# ERC_Sch.net
KiCad netlist of a schematic drawn in EAGLE
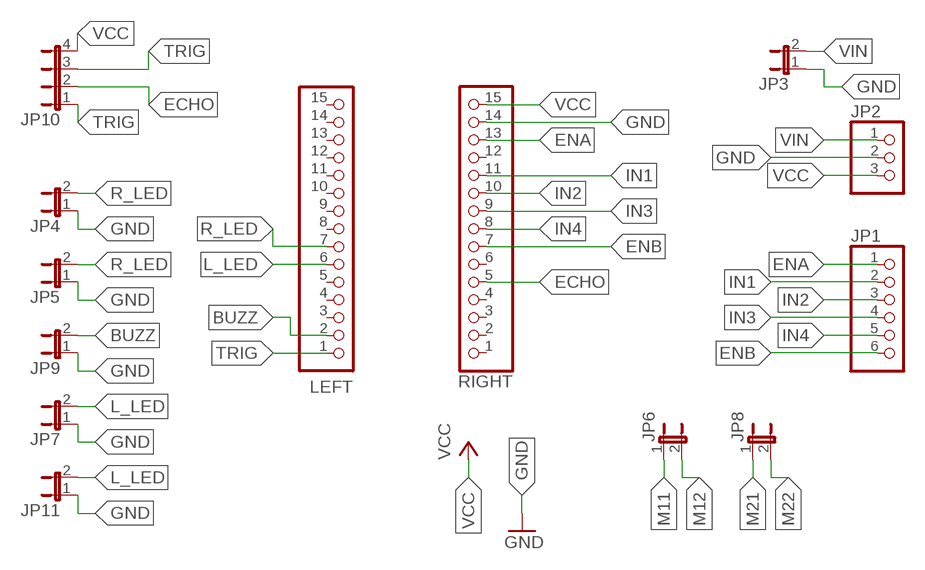
[diagram p0: schematic, sheet 1]

(export (version "E")
  (design (tool "Eeschema 10.0.6"))
  (components
    (comp (ref "JP1")
      (value "PINHD-1X6")
      (footprint "eagle-import:1X06")
      (libsource (lib "eagle-import") (part "PINHD-1X6"))
    )
    (comp (ref "JP2")
      (value "PINHD-1X3")
      (footprint "eagle-import:1X03")
      (libsource (lib "eagle-import") (part "PINHD-1X3"))
    )
    (comp (ref "JP3")
      (value "JP1E")
      (footprint "eagle-import:JP1")
      (libsource (lib "eagle-import") (part "JP1E"))
    )
    (comp (ref "JP4")
      (value "JP1E")
      (footprint "eagle-import:JP1")
      (libsource (lib "eagle-import") (part "JP1E"))
    )
    (comp (ref "JP5")
      (value "JP1E")
      (footprint "eagle-import:JP1")
      (libsource (lib "eagle-import") (part "JP1E"))
    )
    (comp (ref "JP6")
      (value "JP1E")
      (footprint "eagle-import:JP1")
      (libsource (lib "eagle-import") (part "JP1E"))
    )
    (comp (ref "JP7")
      (value "JP1E")
      (footprint "eagle-import:JP1")
      (libsource (lib "eagle-import") (part "JP1E"))
    )
    (comp (ref "JP8")
      (value "JP1E")
      (footprint "eagle-import:JP1")
      (libsource (lib "eagle-import") (part "JP1E"))
    )
    (comp (ref "JP9")
      (value "JP1E")
      (footprint "eagle-import:JP1")
      (libsource (lib "eagle-import") (part "JP1E"))
    )
    (comp (ref "JP10")
      (value "JP4E")
      (footprint "eagle-import:JP4")
      (libsource (lib "eagle-import") (part "JP4E"))
    )
    (comp (ref "JP11")
      (value "JP1E")
      (footprint "eagle-import:JP1")
      (libsource (lib "eagle-import") (part "JP1E"))
    )
    (comp (ref "LEFT")
      (value "PINHD-1X15")
      (footprint "eagle-import:1X15")
      (libsource (lib "eagle-import") (part "PINHD-1X15"))
    )
    (comp (ref "RIGHT")
      (value "PINHD-1X15")
      (footprint "eagle-import:1X15")
      (libsource (lib "eagle-import") (part "PINHD-1X15"))
    )
  )
  (nets
    (net (code "1") (name "BUZZ") (class "Default")
      (node (ref "JP9") (pin "2") (pinfunction "2_2") (pintype "passive"))
      (node (ref "LEFT") (pin "2") (pinfunction "2_2") (pintype "passive"))
    )
    (net (code "2") (name "ECHO") (class "Default")
      (node (ref "JP10") (pin "2") (pinfunction "2_2") (pintype "passive"))
      (node (ref "RIGHT") (pin "5") (pinfunction "5_5") (pintype "passive"))
    )
    (net (code "3") (name "ENA") (class "Default")
      (node (ref "JP1") (pin "1") (pinfunction "1_1") (pintype "passive"))
      (node (ref "RIGHT") (pin "13") (pinfunction "13_13") (pintype "passive"))
    )
    (net (code "4") (name "ENB") (class "Default")
      (node (ref "JP1") (pin "6") (pinfunction "6_6") (pintype "passive"))
      (node (ref "RIGHT") (pin "7") (pinfunction "7_7") (pintype "passive"))
    )
    (net (code "5") (name "GND") (class "Default")
      (node (ref "JP11") (pin "1") (pinfunction "1_1") (pintype "passive"))
      (node (ref "JP2") (pin "2") (pinfunction "2_2") (pintype "passive"))
      (node (ref "JP3") (pin "1") (pinfunction "1_1") (pintype "passive"))
      (node (ref "JP4") (pin "1") (pinfunction "1_1") (pintype "passive"))
      (node (ref "JP5") (pin "1") (pinfunction "1_1") (pintype "passive"))
      (node (ref "JP7") (pin "1") (pinfunction "1_1") (pintype "passive"))
      (node (ref "JP9") (pin "1") (pinfunction "1_1") (pintype "passive"))
      (node (ref "RIGHT") (pin "14") (pinfunction "14_14") (pintype "passive"))
    )
    (net (code "6") (name "IN1") (class "Default")
      (node (ref "JP1") (pin "2") (pinfunction "2_2") (pintype "passive"))
      (node (ref "RIGHT") (pin "11") (pinfunction "11_11") (pintype "passive"))
    )
    (net (code "7") (name "IN2") (class "Default")
      (node (ref "JP1") (pin "3") (pinfunction "3_3") (pintype "passive"))
      (node (ref "RIGHT") (pin "10") (pinfunction "10_10") (pintype "passive"))
    )
    (net (code "8") (name "IN3") (class "Default")
      (node (ref "JP1") (pin "4") (pinfunction "4_4") (pintype "passive"))
      (node (ref "RIGHT") (pin "9") (pinfunction "9_9") (pintype "passive"))
    )
    (net (code "9") (name "IN4") (class "Default")
      (node (ref "JP1") (pin "5") (pinfunction "5_5") (pintype "passive"))
      (node (ref "RIGHT") (pin "8") (pinfunction "8_8") (pintype "passive"))
    )
    (net (code "10") (name "L_LED") (class "Default")
      (node (ref "JP11") (pin "2") (pinfunction "2_2") (pintype "passive"))
      (node (ref "JP7") (pin "2") (pinfunction "2_2") (pintype "passive"))
      (node (ref "LEFT") (pin "6") (pinfunction "6_6") (pintype "passive"))
    )
    (net (code "11") (name "M11") (class "Default")
      (node (ref "JP6") (pin "1") (pinfunction "1_1") (pintype "passive"))
    )
    (net (code "12") (name "M12") (class "Default")
      (node (ref "JP6") (pin "2") (pinfunction "2_2") (pintype "passive"))
    )
    (net (code "13") (name "M21") (class "Default")
      (node (ref "JP8") (pin "1") (pinfunction "1_1") (pintype "passive"))
    )
    (net (code "14") (name "M22") (class "Default")
      (node (ref "JP8") (pin "2") (pinfunction "2_2") (pintype "passive"))
    )
    (net (code "15") (name "R_LED") (class "Default")
      (node (ref "JP4") (pin "2") (pinfunction "2_2") (pintype "passive"))
      (node (ref "JP5") (pin "2") (pinfunction "2_2") (pintype "passive"))
      (node (ref "LEFT") (pin "7") (pinfunction "7_7") (pintype "passive"))
    )
    (net (code "16") (name "TRIG") (class "Default")
      (node (ref "JP10") (pin "1") (pinfunction "1_1") (pintype "passive"))
      (node (ref "JP10") (pin "3") (pinfunction "3_3") (pintype "passive"))
      (node (ref "LEFT") (pin "1") (pinfunction "1_1") (pintype "passive"))
    )
    (net (code "17") (name "VCC") (class "Default")
      (node (ref "JP10") (pin "4") (pinfunction "4_4") (pintype "passive"))
      (node (ref "JP2") (pin "3") (pinfunction "3_3") (pintype "passive"))
      (node (ref "RIGHT") (pin "15") (pinfunction "15_15") (pintype "passive"))
    )
    (net (code "18") (name "VIN") (class "Default")
      (node (ref "JP2") (pin "1") (pinfunction "1_1") (pintype "passive"))
      (node (ref "JP3") (pin "2") (pinfunction "2_2") (pintype "passive"))
    )
    (net (code "19") (name "unconnected-(LEFT-Pad3)") (class "Default")
      (node (ref "LEFT") (pin "3") (pinfunction "3_3") (pintype "passive"))
    )
    (net (code "20") (name "unconnected-(LEFT-Pad4)") (class "Default")
      (node (ref "LEFT") (pin "4") (pinfunction "4_4") (pintype "passive"))
    )
    (net (code "21") (name "unconnected-(LEFT-Pad5)") (class "Default")
      (node (ref "LEFT") (pin "5") (pinfunction "5_5") (pintype "passive"))
    )
    (net (code "22") (name "unconnected-(LEFT-Pad8)") (class "Default")
      (node (ref "LEFT") (pin "8") (pinfunction "8_8") (pintype "passive"))
    )
    (net (code "23") (name "unconnected-(LEFT-Pad9)") (class "Default")
      (node (ref "LEFT") (pin "9") (pinfunction "9_9") (pintype "passive"))
    )
    (net (code "24") (name "unconnected-(LEFT-Pad10)") (class "Default")
      (node (ref "LEFT") (pin "10") (pinfunction "10_10") (pintype "passive"))
    )
    (net (code "25") (name "unconnected-(LEFT-Pad11)") (class "Default")
      (node (ref "LEFT") (pin "11") (pinfunction "11_11") (pintype "passive"))
    )
    (net (code "26") (name "unconnected-(LEFT-Pad12)") (class "Default")
      (node (ref "LEFT") (pin "12") (pinfunction "12_12") (pintype "passive"))
    )
    (net (code "27") (name "unconnected-(LEFT-Pad13)") (class "Default")
      (node (ref "LEFT") (pin "13") (pinfunction "13_13") (pintype "passive"))
    )
    (net (code "28") (name "unconnected-(LEFT-Pad14)") (class "Default")
      (node (ref "LEFT") (pin "14") (pinfunction "14_14") (pintype "passive"))
    )
    (net (code "29") (name "unconnected-(LEFT-Pad15)") (class "Default")
      (node (ref "LEFT") (pin "15") (pinfunction "15_15") (pintype "passive"))
    )
    (net (code "30") (name "unconnected-(RIGHT-Pad1)") (class "Default")
      (node (ref "RIGHT") (pin "1") (pinfunction "1_1") (pintype "passive"))
    )
    (net (code "31") (name "unconnected-(RIGHT-Pad2)") (class "Default")
      (node (ref "RIGHT") (pin "2") (pinfunction "2_2") (pintype "passive"))
    )
    (net (code "32") (name "unconnected-(RIGHT-Pad3)") (class "Default")
      (node (ref "RIGHT") (pin "3") (pinfunction "3_3") (pintype "passive"))
    )
    (net (code "33") (name "unconnected-(RIGHT-Pad4)") (class "Default")
      (node (ref "RIGHT") (pin "4") (pinfunction "4_4") (pintype "passive"))
    )
    (net (code "34") (name "unconnected-(RIGHT-Pad6)") (class "Default")
      (node (ref "RIGHT") (pin "6") (pinfunction "6_6") (pintype "passive"))
    )
    (net (code "35") (name "unconnected-(RIGHT-Pad12)") (class "Default")
      (node (ref "RIGHT") (pin "12") (pinfunction "12_12") (pintype "passive"))
    )
  )
)
